# CMoy-Pro-V_1_0_0_2a.net
KiCad netlist of a schematic drawn in EAGLE
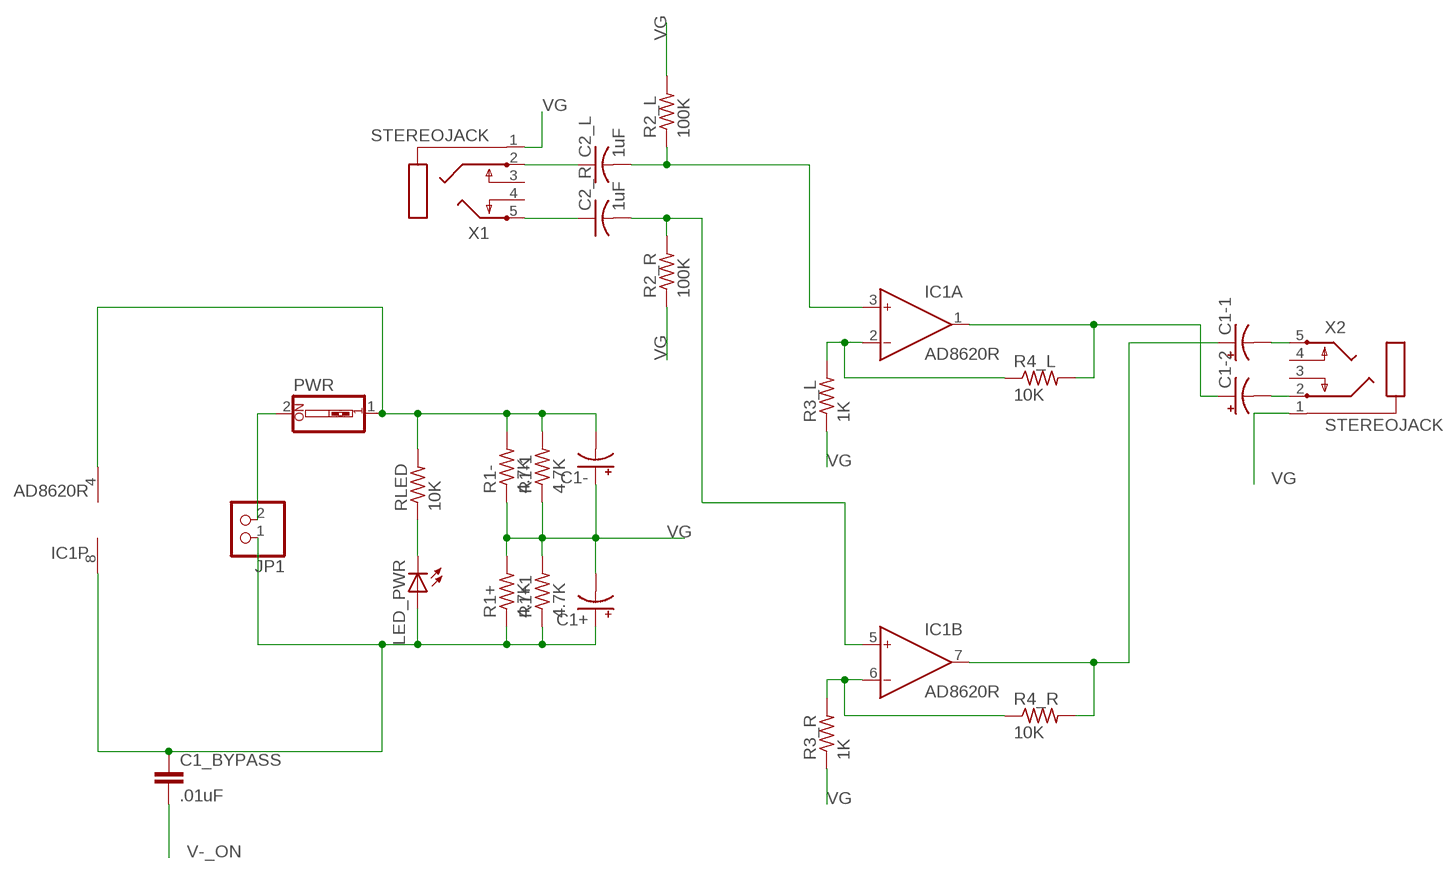
[diagram p0: schematic, sheet 1]

(export (version "E")
  (design (tool "Eeschema 10.0.6"))
  (components
    (comp (ref "C1+")
      (value "CPOL-USE7.5-16")
      (footprint "eagle-import:E7,5-16")
      (libsource (lib "eagle-import") (part "CPOL-USE7.5-16"))
    )
    (comp (ref "C1-")
      (value "CPOL-USE7.5-16")
      (footprint "eagle-import:E7,5-16")
      (libsource (lib "eagle-import") (part "CPOL-USE7.5-16"))
    )
    (comp (ref "C1-1")
      (value "CPOL-USE7.5-16")
      (footprint "eagle-import:E7,5-16")
      (libsource (lib "eagle-import") (part "CPOL-USE7.5-16"))
    )
    (comp (ref "C1-2")
      (value "CPOL-USE7.5-16")
      (footprint "eagle-import:E7,5-16")
      (libsource (lib "eagle-import") (part "CPOL-USE7.5-16"))
    )
    (comp (ref "C1_BYPASS")
      (value ".01uF")
      (footprint "eagle-import:C0402")
      (libsource (lib "eagle-import") (part "C-EUC0402"))
    )
    (comp (ref "C2_L")
      (value "1uF")
      (footprint "eagle-import:C075-042X103")
      (libsource (lib "eagle-import") (part "C-US075-042X103"))
    )
    (comp (ref "C2_R")
      (value "1uF")
      (footprint "eagle-import:C075-042X103")
      (libsource (lib "eagle-import") (part "C-US075-042X103"))
    )
    (comp (ref "IC1")
      (value "AD8620R")
      (footprint "eagle-import:SO8")
      (fields (field (name "MF") "ALTERA CORPORATION") (field (name "MPN") "AD8620ARZ"))
      (libsource (lib "eagle-import") (part "AD8620R"))
    )
    (comp (ref "JP1")
      (value "PINHD-1X2")
      (footprint "eagle-import:1X02")
      (libsource (lib "eagle-import") (part "PINHD-1X2"))
    )
    (comp (ref "LED_PWR")
      (value "LED3MM")
      (footprint "eagle-import:LED3MM")
      (libsource (lib "eagle-import") (part "LED3MM"))
    )
    (comp (ref "PWR")
      (value "SW_DIP-1")
      (footprint "eagle-import:EDG-01")
      (libsource (lib "eagle-import") (part "SW_DIP-1"))
    )
    (comp (ref "R1+")
      (value "4.7K")
      (footprint "eagle-import:0207_7")
      (libsource (lib "eagle-import") (part "R-US_0207/7"))
    )
    (comp (ref "R1+1")
      (value "4.7K")
      (footprint "eagle-import:0207_7")
      (libsource (lib "eagle-import") (part "R-US_0207/7"))
    )
    (comp (ref "R1-")
      (value "4.7K")
      (footprint "eagle-import:0207_7")
      (libsource (lib "eagle-import") (part "R-US_0207/7"))
    )
    (comp (ref "R1-1")
      (value "4.7K")
      (footprint "eagle-import:0207_7")
      (libsource (lib "eagle-import") (part "R-US_0207/7"))
    )
    (comp (ref "R2_L")
      (value "100K")
      (footprint "eagle-import:0207_7")
      (libsource (lib "eagle-import") (part "R-US_0207/7"))
    )
    (comp (ref "R2_R")
      (value "100K")
      (footprint "eagle-import:0207_7")
      (libsource (lib "eagle-import") (part "R-US_0207/7"))
    )
    (comp (ref "R3_L")
      (value "1K")
      (footprint "eagle-import:0207_7")
      (libsource (lib "eagle-import") (part "R-US_0207/7"))
    )
    (comp (ref "R3_R")
      (value "1K")
      (footprint "eagle-import:0207_7")
      (libsource (lib "eagle-import") (part "R-US_0207/7"))
    )
    (comp (ref "R4_L")
      (value "10K")
      (footprint "eagle-import:0207_7")
      (libsource (lib "eagle-import") (part "R-US_0207/7"))
    )
    (comp (ref "R4_R")
      (value "10K")
      (footprint "eagle-import:0207_7")
      (libsource (lib "eagle-import") (part "R-US_0207/7"))
    )
    (comp (ref "RLED")
      (value "10K")
      (footprint "eagle-import:0207_7")
      (libsource (lib "eagle-import") (part "R-US_0207/7"))
    )
    (comp (ref "X1")
      (value "STEREOJACK")
      (footprint "eagle-import:STX3100")
      (libsource (lib "eagle-import") (part "STEREOJACK"))
    )
    (comp (ref "X2")
      (value "STEREOJACK")
      (footprint "eagle-import:STX3100")
      (libsource (lib "eagle-import") (part "STEREOJACK"))
    )
  )
  (nets
    (net (code "1") (name "/V-_ON") (class "Default")
      (node (ref "C1-") (pin "-") (pinfunction "-_-") (pintype "passive"))
      (node (ref "C1_BYPASS") (pin "2") (pinfunction "2_2") (pintype "passive"))
      (node (ref "IC1") (pin "4") (pinfunction "V-_4") (pintype "power_in"))
      (node (ref "PWR") (pin "1") (pinfunction "1_1") (pintype "passive"))
      (node (ref "R1-") (pin "2") (pinfunction "2_2") (pintype "passive"))
      (node (ref "R1-1") (pin "2") (pinfunction "2_2") (pintype "passive"))
      (node (ref "RLED") (pin "2") (pinfunction "2_2") (pintype "passive"))
    )
    (net (code "2") (name "/VG") (class "Default")
      (node (ref "C1+") (pin "-") (pinfunction "-_-") (pintype "passive"))
      (node (ref "C1-") (pin "+") (pinfunction "+_+") (pintype "passive"))
      (node (ref "R1+") (pin "2") (pinfunction "2_2") (pintype "passive"))
      (node (ref "R1+1") (pin "2") (pinfunction "2_2") (pintype "passive"))
      (node (ref "R1-") (pin "1") (pinfunction "1_1") (pintype "passive"))
      (node (ref "R1-1") (pin "1") (pinfunction "1_1") (pintype "passive"))
      (node (ref "R2_L") (pin "2") (pinfunction "2_2") (pintype "passive"))
      (node (ref "R2_R") (pin "1") (pinfunction "1_1") (pintype "passive"))
      (node (ref "R3_L") (pin "1") (pinfunction "1_1") (pintype "passive"))
      (node (ref "R3_R") (pin "1") (pinfunction "1_1") (pintype "passive"))
      (node (ref "X1") (pin "1") (pinfunction "1_1") (pintype "passive"))
      (node (ref "X2") (pin "1") (pinfunction "1_1") (pintype "passive"))
    )
    (net (code "3") (name "Net-(C1-1-Pad-)") (class "Default")
      (node (ref "C1-1") (pin "-") (pinfunction "-_-") (pintype "passive"))
      (node (ref "X2") (pin "5") (pinfunction "5_5") (pintype "passive"))
    )
    (net (code "4") (name "Net-(C1-2-Pad-)") (class "Default")
      (node (ref "C1-2") (pin "-") (pinfunction "-_-") (pintype "passive"))
      (node (ref "X2") (pin "2") (pinfunction "2_2") (pintype "passive"))
    )
    (net (code "5") (name "Net-(C2_L-Pad1)") (class "Default")
      (node (ref "C2_L") (pin "1") (pinfunction "1_1") (pintype "passive"))
      (node (ref "X1") (pin "2") (pinfunction "2_2") (pintype "passive"))
    )
    (net (code "6") (name "Net-(C2_R-Pad1)") (class "Default")
      (node (ref "C2_R") (pin "1") (pinfunction "1_1") (pintype "passive"))
      (node (ref "X1") (pin "5") (pinfunction "5_5") (pintype "passive"))
    )
    (net (code "7") (name "Net-(IC1A-IN+)") (class "Default")
      (node (ref "C2_L") (pin "2") (pinfunction "2_2") (pintype "passive"))
      (node (ref "IC1") (pin "3") (pinfunction "IN+_3") (pintype "input"))
      (node (ref "R2_L") (pin "1") (pinfunction "1_1") (pintype "passive"))
    )
    (net (code "8") (name "Net-(IC1A-IN-)") (class "Default")
      (node (ref "IC1") (pin "2") (pinfunction "IN-_2") (pintype "input"))
      (node (ref "R3_L") (pin "2") (pinfunction "2_2") (pintype "passive"))
      (node (ref "R4_L") (pin "1") (pinfunction "1_1") (pintype "passive"))
    )
    (net (code "9") (name "Net-(IC1A-OUT)") (class "Default")
      (node (ref "C1-2") (pin "+") (pinfunction "+_+") (pintype "passive"))
      (node (ref "IC1") (pin "1") (pinfunction "OUT_1") (pintype "output"))
      (node (ref "R4_L") (pin "2") (pinfunction "2_2") (pintype "passive"))
    )
    (net (code "10") (name "Net-(IC1B-IN+)") (class "Default")
      (node (ref "C2_R") (pin "2") (pinfunction "2_2") (pintype "passive"))
      (node (ref "IC1") (pin "5") (pinfunction "IN+_5") (pintype "input"))
      (node (ref "R2_R") (pin "2") (pinfunction "2_2") (pintype "passive"))
    )
    (net (code "11") (name "Net-(IC1B-IN-)") (class "Default")
      (node (ref "IC1") (pin "6") (pinfunction "IN-_6") (pintype "input"))
      (node (ref "R3_R") (pin "2") (pinfunction "2_2") (pintype "passive"))
      (node (ref "R4_R") (pin "1") (pinfunction "1_1") (pintype "passive"))
    )
    (net (code "12") (name "Net-(IC1B-OUT)") (class "Default")
      (node (ref "C1-1") (pin "+") (pinfunction "+_+") (pintype "passive"))
      (node (ref "IC1") (pin "7") (pinfunction "OUT_7") (pintype "output"))
      (node (ref "R4_R") (pin "2") (pinfunction "2_2") (pintype "passive"))
    )
    (net (code "13") (name "Net-(IC1C-V+)") (class "Default")
      (node (ref "C1+") (pin "+") (pinfunction "+_+") (pintype "passive"))
      (node (ref "C1_BYPASS") (pin "1") (pinfunction "1_1") (pintype "passive"))
      (node (ref "IC1") (pin "8") (pinfunction "V+_8") (pintype "power_in"))
      (node (ref "JP1") (pin "1") (pinfunction "1_1") (pintype "passive"))
      (node (ref "LED_PWR") (pin "A") (pinfunction "A_A") (pintype "passive"))
      (node (ref "R1+") (pin "1") (pinfunction "1_1") (pintype "passive"))
      (node (ref "R1+1") (pin "1") (pinfunction "1_1") (pintype "passive"))
    )
    (net (code "14") (name "Net-(JP1-Pad2)") (class "Default")
      (node (ref "JP1") (pin "2") (pinfunction "2_2") (pintype "passive"))
      (node (ref "PWR") (pin "2") (pinfunction "2_2") (pintype "passive"))
    )
    (net (code "15") (name "Net-(LED_PWR-C)") (class "Default")
      (node (ref "LED_PWR") (pin "K") (pinfunction "C_K") (pintype "passive"))
      (node (ref "RLED") (pin "1") (pinfunction "1_1") (pintype "passive"))
    )
    (net (code "16") (name "unconnected-(X1-Pad3)") (class "Default")
      (node (ref "X1") (pin "3") (pinfunction "3_3") (pintype "passive"))
    )
    (net (code "17") (name "unconnected-(X1-Pad4)") (class "Default")
      (node (ref "X1") (pin "4") (pinfunction "4_4") (pintype "passive"))
    )
    (net (code "18") (name "unconnected-(X2-Pad3)") (class "Default")
      (node (ref "X2") (pin "3") (pinfunction "3_3") (pintype "passive"))
    )
    (net (code "19") (name "unconnected-(X2-Pad4)") (class "Default")
      (node (ref "X2") (pin "4") (pinfunction "4_4") (pintype "passive"))
    )
  )
)
